# Schematics_HUMA-mini.net
KiCad netlist of a schematic drawn in Altium Designer
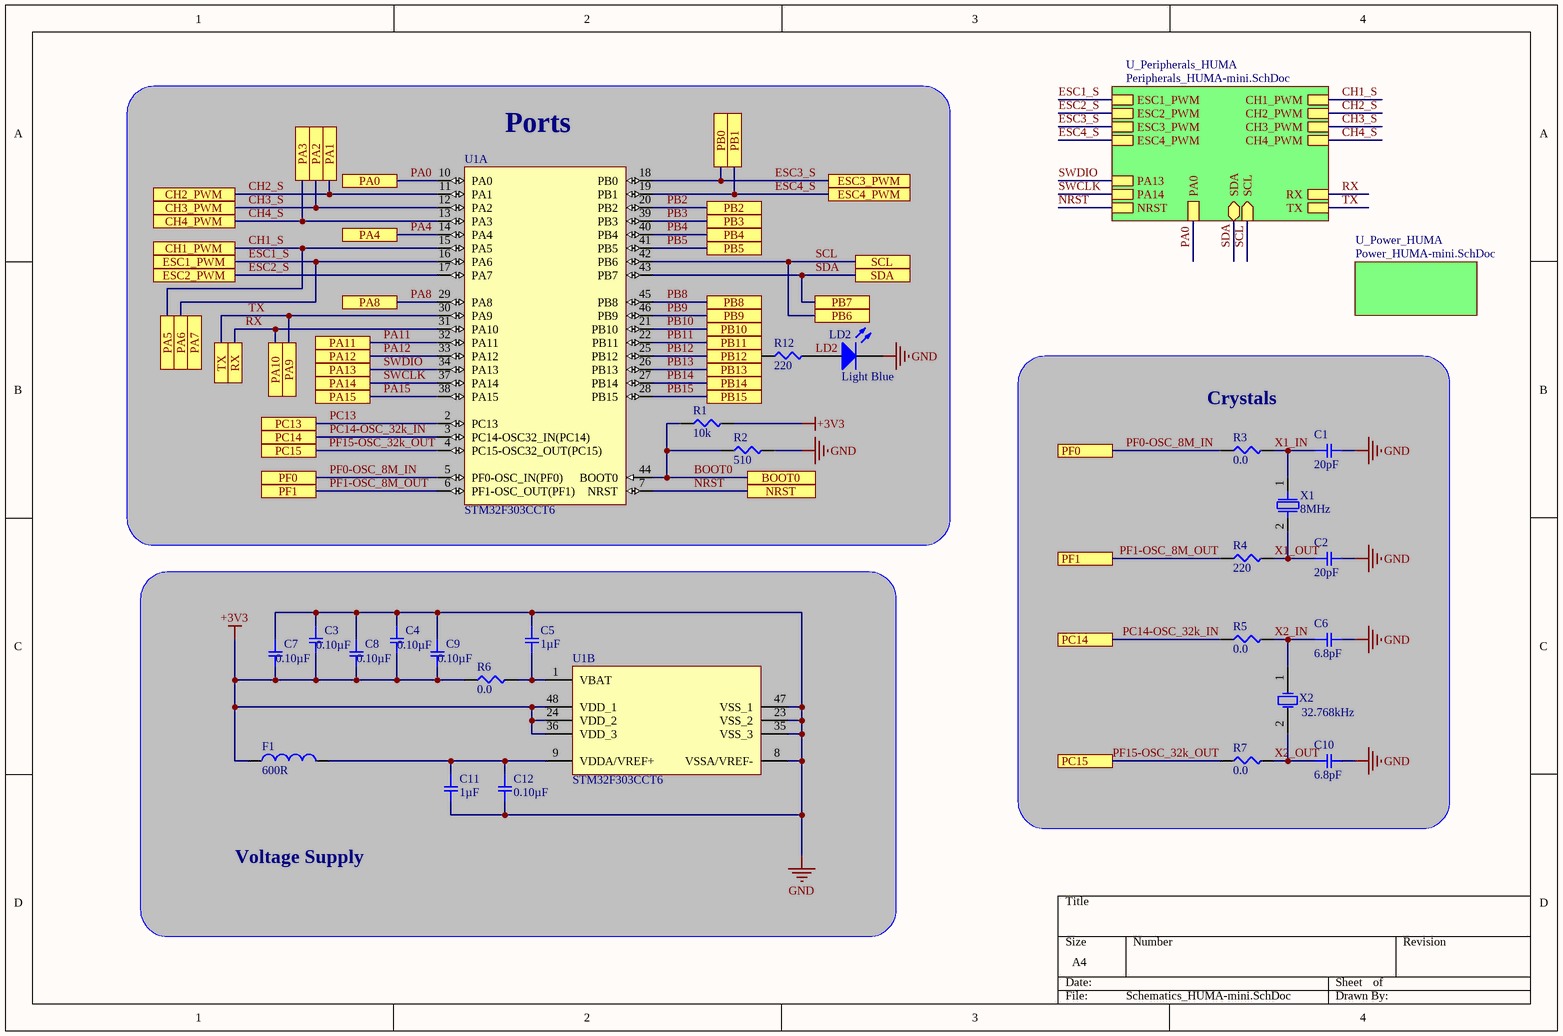
[diagram p0: Schematics_HUMA-mini.SchDoc]

(export (version "E")
  (design (tool "Eeschema 10.0.6"))
  (components
    (comp (ref "C1")
      (value "20pF")
      (footprint "SMD-0805C")
      (description "CAP CER 20PF 50V NP0 0805")
      (fields
        (field (name "DIGI-KEY PART NUMBER") "490-3607-1-ND")
        (field (name "PART NUMBER") "GQM2195C1H200JB01D")
      )
      (libsource (lib "Capacitors_Murata") (part "GQM2195C1H200JB01D"))
    )
    (comp (ref "C2")
      (value "20pF")
      (footprint "SMD-0805C")
      (description "CAP CER 20PF 50V NP0 0805")
      (fields
        (field (name "DIGI-KEY PART NUMBER") "490-3607-1-ND")
        (field (name "PART NUMBER") "GQM2195C1H200JB01D")
      )
      (libsource (lib "Capacitors_Murata") (part "GQM2195C1H200JB01D"))
    )
    (comp (ref "C3")
      (value "0.10µF")
      (footprint "SMD-0805C")
      (description "CAP CER 0.1UF 25V X7R 0805")
      (fields
        (field (name "DIGI-KEY PART NUMBER") "490-12754-1-ND")
        (field (name "PART NUMBER") "GRM219R71E104KA01D")
      )
      (libsource (lib "Capacitors_Murata") (part "GRM219R71E104KA01D"))
    )
    (comp (ref "C4")
      (value "0.10µF")
      (footprint "SMD-0805C")
      (description "CAP CER 0.1UF 25V X7R 0805")
      (fields
        (field (name "DIGI-KEY PART NUMBER") "490-12754-1-ND")
        (field (name "PART NUMBER") "GRM219R71E104KA01D")
      )
      (libsource (lib "Capacitors_Murata") (part "GRM219R71E104KA01D"))
    )
    (comp (ref "C5")
      (value "1µF")
      (footprint "SMD-0805C")
      (description "CAP CER 1UF 25V X5R 0805")
      (fields
        (field (name "DIGI-KEY PART NUMBER") "490-12386-1-ND")
        (field (name "PART NUMBER") "GRT21BR61E105KE13L")
      )
      (libsource (lib "Capacitors_Murata") (part "GRT21BR61E105KE13L"))
    )
    (comp (ref "C6")
      (value "6.8pF")
      (footprint "SMD-0805C")
      (description "CAP CER 6.8PF 100V NP0 0805")
      (fields
        (field (name "DIGI-KEY PART NUMBER") "490-8142-1-ND")
        (field (name "PART NUMBER") "GQM2195C2A6R8DB01D")
      )
      (libsource (lib "Capacitors_Murata") (part "GQM2195C2A6R8DB01D"))
    )
    (comp (ref "C7")
      (value "0.10µF")
      (footprint "SMD-0805C")
      (description "CAP CER 0.1UF 25V X7R 0805")
      (fields
        (field (name "DIGI-KEY PART NUMBER") "490-12754-1-ND")
        (field (name "PART NUMBER") "GRM219R71E104KA01D")
      )
      (libsource (lib "Capacitors_Murata") (part "GRM219R71E104KA01D"))
    )
    (comp (ref "C8")
      (value "0.10µF")
      (footprint "SMD-0805C")
      (description "CAP CER 0.1UF 25V X7R 0805")
      (fields
        (field (name "DIGI-KEY PART NUMBER") "490-12754-1-ND")
        (field (name "PART NUMBER") "GRM219R71E104KA01D")
      )
      (libsource (lib "Capacitors_Murata") (part "GRM219R71E104KA01D"))
    )
    (comp (ref "C9")
      (value "0.10µF")
      (footprint "SMD-0805C")
      (description "CAP CER 0.1UF 25V X7R 0805")
      (fields
        (field (name "DIGI-KEY PART NUMBER") "490-12754-1-ND")
        (field (name "PART NUMBER") "GRM219R71E104KA01D")
      )
      (libsource (lib "Capacitors_Murata") (part "GRM219R71E104KA01D"))
    )
    (comp (ref "C10")
      (value "6.8pF")
      (footprint "SMD-0805C")
      (description "CAP CER 6.8PF 100V NP0 0805")
      (fields
        (field (name "DIGI-KEY PART NUMBER") "490-8142-1-ND")
        (field (name "PART NUMBER") "GQM2195C2A6R8DB01D")
      )
      (libsource (lib "Capacitors_Murata") (part "GQM2195C2A6R8DB01D"))
    )
    (comp (ref "C11")
      (value "1µF")
      (footprint "SMD-0805C")
      (description "CAP CER 1UF 25V X5R 0805")
      (fields
        (field (name "DIGI-KEY PART NUMBER") "490-12386-1-ND")
        (field (name "PART NUMBER") "GRT21BR61E105KE13L")
      )
      (libsource (lib "Capacitors_Murata") (part "GRT21BR61E105KE13L"))
    )
    (comp (ref "C12")
      (value "0.10µF")
      (footprint "SMD-0805C")
      (description "CAP CER 0.1UF 25V X7R 0805")
      (fields
        (field (name "DIGI-KEY PART NUMBER") "490-12754-1-ND")
        (field (name "PART NUMBER") "GRM219R71E104KA01D")
      )
      (libsource (lib "Capacitors_Murata") (part "GRM219R71E104KA01D"))
    )
    (comp (ref "F1")
      (value "FERRITE BEAD 600 OHM 1206 1LN")
      (footprint "IND_0805")
      (description "600 Ohms @ 100MHz 1 Signal Line Ferrite Bead 1206 (3216 Metric) 2.5A 70mOhm")
      (fields (field (name "DEGER") "600R"))
      (libsource (lib "Bobin-Ferit") (part "Ferrite 600ohm 1206(742792118)"))
    )
    (comp (ref "LD2")
      (value "Light Blue")
      (footprint "Type 3mm")
      (description "THT LED round mono-color waterclear, WL-TMRW , Blue")
      (fields (field (name "PARTNUMBER") "151033BS03000"))
      (libsource (lib "WL-TMRW THT LED round mono-color waterclear") (part "151033BS03000"))
    )
    (comp (ref "R1")
      (value "10k")
      (footprint "SMD-0805-RES")
      (description "RES SMD 10K OHM 1% 1/8W 0805")
      (fields
        (field (name "PART NUMBER") "ERJ-6ENF1002V")
        (field (name "DIGI-KEY PART NUMBER") "P10.0KCCT-ND")
      )
      (libsource (lib "Resistors_Panasonic") (part "ERJ-6ENF1002V"))
    )
    (comp (ref "R2")
      (value "510")
      (footprint "SMD-0805-RES")
      (description "RES SMD 510 OHM 5% 1/2W 0805")
      (fields (field (name "PART NUMBER") "ERJ-P06J511V") (field (name "DIGI-KEY PART NUMBER") "P510ADCT-ND"))
      (libsource (lib "Resistors_Panasonic") (part "ERJ-P06J511V"))
    )
    (comp (ref "R3")
      (value "0.0")
      (footprint "SMD-0805-RES")
      (description "RES SMD 0.0 OHM JUMPER 1/8W 0805")
      (fields (field (name "PART NUMBER") "ERJ-6GEY0R00V") (field (name "DIGI-KEY PART NUMBER") "P0.0ACT-ND"))
      (libsource (lib "Resistors_Panasonic") (part "ERJ-6GEY0R00V"))
    )
    (comp (ref "R4")
      (value "220")
      (footprint "SMD-0805-RES")
      (description "RES SMD 220 OHM 1% 1/8W 0805")
      (fields (field (name "PART NUMBER") "ERJ-6ENF2200V") (field (name "DIGI-KEY PART NUMBER") "P220CCT-ND"))
      (libsource (lib "Resistors_Panasonic") (part "ERJ-6ENF2200V"))
    )
    (comp (ref "R5")
      (value "0.0")
      (footprint "SMD-0805-RES")
      (description "RES SMD 0.0 OHM JUMPER 1/8W 0805")
      (fields (field (name "PART NUMBER") "ERJ-6GEY0R00V") (field (name "DIGI-KEY PART NUMBER") "P0.0ACT-ND"))
      (libsource (lib "Resistors_Panasonic") (part "ERJ-6GEY0R00V"))
    )
    (comp (ref "R6")
      (value "0.0")
      (footprint "SMD-0805-RES")
      (description "RES SMD 0.0 OHM JUMPER 1/8W 0805")
      (fields (field (name "PART NUMBER") "ERJ-6GEY0R00V") (field (name "DIGI-KEY PART NUMBER") "P0.0ACT-ND"))
      (libsource (lib "Resistors_Panasonic") (part "ERJ-6GEY0R00V"))
    )
    (comp (ref "R7")
      (value "0.0")
      (footprint "SMD-0805-RES")
      (description "RES SMD 0.0 OHM JUMPER 1/8W 0805")
      (fields (field (name "PART NUMBER") "ERJ-6GEY0R00V") (field (name "DIGI-KEY PART NUMBER") "P0.0ACT-ND"))
      (libsource (lib "Resistors_Panasonic") (part "ERJ-6GEY0R00V"))
    )
    (comp (ref "R12")
      (value "220")
      (footprint "SMD-0805-RES")
      (description "RES SMD 220 OHM 5% 1/2W 0805")
      (fields (field (name "PART NUMBER") "ERJ-P6WJ221V") (field (name "DIGI-KEY PART NUMBER") "P16946CT-ND"))
      (libsource (lib "Resistors_Panasonic") (part "ERJ-P6WJ221V"))
    )
    (comp (ref "U1")
      (value "STM32F303CCT6")
      (footprint "STM-LQFP48_N")
      (libsource (lib "STMicroelectronics STM32 F3") (part "STM32F303CCT6"))
    )
    (comp (ref "X1")
      (value "8MHz")
      (footprint "OSC488W43P488L465H350Q2P")
      (description "Crystal; Frequency: 8MHz; Frequency")
      (fields (field (name "MP") "X14M745600L225") (field (name "MF") "AEL Crystals"))
      (libsource (lib "XTAL8MHz") (part "XTAL8MHz"))
    )
    (comp (ref "X2")
      (value "32.768kHz")
      (footprint "R38")
      (description "Crystal Oscillator")
      (fields (field (name "Comment") "XTAL") (field (name "PUBLISHER") "Altium Limited"))
      (libsource (lib "Miscellaneous Devices") (part "XTAL"))
    )
  )
  (nets
    (net (code "1") (name "+3V3") (class "Default")
      (node (ref "C3") (pin "2") (pinfunction "2_2") (pintype "passive"))
      (node (ref "C4") (pin "2") (pinfunction "2_2") (pintype "passive"))
      (node (ref "C7") (pin "2") (pinfunction "2_2") (pintype "passive"))
      (node (ref "C8") (pin "2") (pinfunction "2_2") (pintype "passive"))
      (node (ref "C9") (pin "2") (pinfunction "2_2") (pintype "passive"))
      (node (ref "F1") (pin "1") (pinfunction "1_1") (pintype "passive"))
      (node (ref "R1") (pin "2") (pinfunction "2_2") (pintype "passive"))
      (node (ref "R6") (pin "1") (pinfunction "1_1") (pintype "passive"))
      (node (ref "U1") (pin "24") (pinfunction "VDD_2_24") (pintype "power_in"))
      (node (ref "U1") (pin "36") (pinfunction "VDD_3_36") (pintype "power_in"))
      (node (ref "U1") (pin "48") (pinfunction "VDD_1_48") (pintype "power_in"))
    )
    (net (code "2") (name "/BOOT0") (class "Default")
      (node (ref "R1") (pin "1") (pinfunction "1_1") (pintype "passive"))
      (node (ref "R2") (pin "1") (pinfunction "1_1") (pintype "passive"))
      (node (ref "U1") (pin "44") (pinfunction "BOOT0_44") (pintype "input"))
    )
    (net (code "3") (name "/CH1_S") (class "Default")
      (node (ref "U1") (pin "15") (pinfunction "PA5_15") (pintype "bidirectional"))
    )
    (net (code "4") (name "/CH2_S") (class "Default")
      (node (ref "U1") (pin "11") (pinfunction "PA1_11") (pintype "bidirectional"))
    )
    (net (code "5") (name "/CH3_S") (class "Default")
      (node (ref "U1") (pin "12") (pinfunction "PA2_12") (pintype "bidirectional"))
    )
    (net (code "6") (name "/CH4_S") (class "Default")
      (node (ref "U1") (pin "13") (pinfunction "PA3_13") (pintype "bidirectional"))
    )
    (net (code "7") (name "/ESC1_S") (class "Default")
      (node (ref "U1") (pin "16") (pinfunction "PA6_16") (pintype "bidirectional"))
    )
    (net (code "8") (name "/ESC2_S") (class "Default")
      (node (ref "U1") (pin "17") (pinfunction "PA7_17") (pintype "bidirectional"))
    )
    (net (code "9") (name "/ESC3_S") (class "Default")
      (node (ref "U1") (pin "18") (pinfunction "PB0_18") (pintype "bidirectional"))
    )
    (net (code "10") (name "/ESC4_S") (class "Default")
      (node (ref "U1") (pin "19") (pinfunction "PB1_19") (pintype "bidirectional"))
    )
    (net (code "11") (name "/LD2") (class "Default")
      (node (ref "LD2") (pin "2") (pinfunction "A_2") (pintype "passive"))
      (node (ref "R12") (pin "2") (pinfunction "2_2") (pintype "passive"))
    )
    (net (code "12") (name "/NRST") (class "Default")
      (node (ref "U1") (pin "7") (pinfunction "NRST_7") (pintype "bidirectional"))
    )
    (net (code "13") (name "/PA0") (class "Default")
      (node (ref "U1") (pin "10") (pinfunction "PA0_10") (pintype "bidirectional"))
    )
    (net (code "14") (name "/PA4") (class "Default")
      (node (ref "U1") (pin "14") (pinfunction "PA4_14") (pintype "bidirectional"))
    )
    (net (code "16") (name "/PA8") (class "Default")
      (node (ref "U1") (pin "29") (pinfunction "PA8_29") (pintype "bidirectional"))
    )
    (net (code "17") (name "/PA11") (class "Default")
      (node (ref "U1") (pin "32") (pinfunction "PA11_32") (pintype "bidirectional"))
    )
    (net (code "18") (name "/PA12") (class "Default")
      (node (ref "U1") (pin "33") (pinfunction "PA12_33") (pintype "bidirectional"))
    )
    (net (code "19") (name "/PA15") (class "Default")
      (node (ref "U1") (pin "38") (pinfunction "PA15_38") (pintype "bidirectional"))
    )
    (net (code "20") (name "/PB2") (class "Default")
      (node (ref "U1") (pin "20") (pinfunction "PB2_20") (pintype "bidirectional"))
    )
    (net (code "21") (name "/PB3") (class "Default")
      (node (ref "U1") (pin "39") (pinfunction "PB3_39") (pintype "bidirectional"))
    )
    (net (code "22") (name "/PB4") (class "Default")
      (node (ref "U1") (pin "40") (pinfunction "PB4_40") (pintype "bidirectional"))
    )
    (net (code "23") (name "/PB5") (class "Default")
      (node (ref "U1") (pin "41") (pinfunction "PB5_41") (pintype "bidirectional"))
    )
    (net (code "24") (name "/PB8") (class "Default")
      (node (ref "U1") (pin "45") (pinfunction "PB8_45") (pintype "bidirectional"))
    )
    (net (code "25") (name "/PB9") (class "Default")
      (node (ref "U1") (pin "46") (pinfunction "PB9_46") (pintype "bidirectional"))
    )
    (net (code "26") (name "/PB10") (class "Default")
      (node (ref "U1") (pin "21") (pinfunction "PB10_21") (pintype "bidirectional"))
    )
    (net (code "27") (name "/PB11") (class "Default")
      (node (ref "U1") (pin "22") (pinfunction "PB11_22") (pintype "bidirectional"))
    )
    (net (code "28") (name "/PB12") (class "Default")
      (node (ref "R12") (pin "1") (pinfunction "1_1") (pintype "passive"))
      (node (ref "U1") (pin "25") (pinfunction "PB12_25") (pintype "bidirectional"))
    )
    (net (code "29") (name "/PB13") (class "Default")
      (node (ref "U1") (pin "26") (pinfunction "PB13_26") (pintype "bidirectional"))
    )
    (net (code "30") (name "/PB14") (class "Default")
      (node (ref "U1") (pin "27") (pinfunction "PB14_27") (pintype "bidirectional"))
    )
    (net (code "31") (name "/PB15") (class "Default")
      (node (ref "U1") (pin "28") (pinfunction "PB15_28") (pintype "bidirectional"))
    )
    (net (code "32") (name "/PC13") (class "Default")
      (node (ref "U1") (pin "2") (pinfunction "PC13_2") (pintype "bidirectional"))
    )
    (net (code "33") (name "/PC14-OSC_32k_IN") (class "Default")
      (node (ref "R5") (pin "1") (pinfunction "1_1") (pintype "passive"))
      (node (ref "U1") (pin "3") (pinfunction "PC14-OSC32_IN(PC14)_3") (pintype "bidirectional"))
    )
    (net (code "34") (name "/PF0-OSC_8M_IN") (class "Default")
      (node (ref "R3") (pin "1") (pinfunction "1_1") (pintype "passive"))
      (node (ref "U1") (pin "5") (pinfunction "PF0-OSC_IN(PF0)_5") (pintype "bidirectional"))
    )
    (net (code "35") (name "/PF1-OSC_8M_OUT") (class "Default")
      (node (ref "R4") (pin "1") (pinfunction "1_1") (pintype "passive"))
      (node (ref "U1") (pin "6") (pinfunction "PF1-OSC_OUT(PF1)_6") (pintype "bidirectional"))
    )
    (net (code "36") (name "/PF15-OSC_32k_OUT") (class "Default")
      (node (ref "R7") (pin "1") (pinfunction "1_1") (pintype "passive"))
      (node (ref "U1") (pin "4") (pinfunction "PC15-OSC32_OUT(PC15)_4") (pintype "bidirectional"))
    )
    (net (code "37") (name "/RX") (class "Default")
      (node (ref "U1") (pin "31") (pinfunction "PA10_31") (pintype "bidirectional"))
    )
    (net (code "38") (name "/SCL") (class "Default")
      (node (ref "U1") (pin "42") (pinfunction "PB6_42") (pintype "bidirectional"))
    )
    (net (code "39") (name "/SDA") (class "Default")
      (node (ref "U1") (pin "43") (pinfunction "PB7_43") (pintype "bidirectional"))
    )
    (net (code "40") (name "/SWCLK") (class "Default")
      (node (ref "U1") (pin "37") (pinfunction "PA14_37") (pintype "bidirectional"))
    )
    (net (code "41") (name "/SWDIO") (class "Default")
      (node (ref "U1") (pin "34") (pinfunction "PA13_34") (pintype "bidirectional"))
    )
    (net (code "42") (name "/TX") (class "Default")
      (node (ref "U1") (pin "30") (pinfunction "PA9_30") (pintype "bidirectional"))
    )
    (net (code "43") (name "/X1_IN") (class "Default")
      (node (ref "C1") (pin "1") (pinfunction "1_1") (pintype "passive"))
      (node (ref "R3") (pin "2") (pinfunction "2_2") (pintype "passive"))
      (node (ref "X1") (pin "1") (pinfunction "1_1") (pintype "passive"))
    )
    (net (code "44") (name "/X1_OUT") (class "Default")
      (node (ref "C2") (pin "1") (pinfunction "1_1") (pintype "passive"))
      (node (ref "R4") (pin "2") (pinfunction "2_2") (pintype "passive"))
      (node (ref "X1") (pin "2") (pinfunction "2_2") (pintype "passive"))
    )
    (net (code "45") (name "/X2_IN") (class "Default")
      (node (ref "C6") (pin "1") (pinfunction "1_1") (pintype "passive"))
      (node (ref "R5") (pin "2") (pinfunction "2_2") (pintype "passive"))
      (node (ref "X2") (pin "1") (pinfunction "OSC1_1") (pintype "passive"))
    )
    (net (code "46") (name "/X2_OUT") (class "Default")
      (node (ref "C10") (pin "1") (pinfunction "1_1") (pintype "passive"))
      (node (ref "R7") (pin "2") (pinfunction "2_2") (pintype "passive"))
      (node (ref "X2") (pin "2") (pinfunction "OSC2_2") (pintype "passive"))
    )
    (net (code "47") (name "GND") (class "Default")
      (node (ref "C1") (pin "2") (pinfunction "2_2") (pintype "passive"))
      (node (ref "C10") (pin "2") (pinfunction "2_2") (pintype "passive"))
      (node (ref "C11") (pin "2") (pinfunction "2_2") (pintype "passive"))
      (node (ref "C12") (pin "2") (pinfunction "2_2") (pintype "passive"))
      (node (ref "C2") (pin "2") (pinfunction "2_2") (pintype "passive"))
      (node (ref "C3") (pin "1") (pinfunction "1_1") (pintype "passive"))
      (node (ref "C4") (pin "1") (pinfunction "1_1") (pintype "passive"))
      (node (ref "C5") (pin "1") (pinfunction "1_1") (pintype "passive"))
      (node (ref "C6") (pin "2") (pinfunction "2_2") (pintype "passive"))
      (node (ref "C7") (pin "1") (pinfunction "1_1") (pintype "passive"))
      (node (ref "C8") (pin "1") (pinfunction "1_1") (pintype "passive"))
      (node (ref "C9") (pin "1") (pinfunction "1_1") (pintype "passive"))
      (node (ref "LD2") (pin "1") (pinfunction "K_1") (pintype "passive"))
      (node (ref "R2") (pin "2") (pinfunction "2_2") (pintype "passive"))
      (node (ref "U1") (pin "23") (pinfunction "VSS_2_23") (pintype "power_in"))
      (node (ref "U1") (pin "35") (pinfunction "VSS_3_35") (pintype "power_in"))
      (node (ref "U1") (pin "47") (pinfunction "VSS_1_47") (pintype "power_in"))
      (node (ref "U1") (pin "8") (pinfunction "VSSA/VREF-_8") (pintype "power_in"))
    )
    (net (code "48") (name "Net-(U1B-VBAT)") (class "Default")
      (node (ref "C5") (pin "2") (pinfunction "2_2") (pintype "passive"))
      (node (ref "R6") (pin "2") (pinfunction "2_2") (pintype "passive"))
      (node (ref "U1") (pin "1") (pinfunction "VBAT_1") (pintype "power_in"))
    )
    (net (code "49") (name "Net-(U1B-VDDA{slash}VREF+)") (class "Default")
      (node (ref "C11") (pin "1") (pinfunction "1_1") (pintype "passive"))
      (node (ref "C12") (pin "1") (pinfunction "1_1") (pintype "passive"))
      (node (ref "F1") (pin "2") (pinfunction "2_2") (pintype "passive"))
      (node (ref "U1") (pin "9") (pinfunction "VDDA/VREF+_9") (pintype "power_in"))
    )
  )
)
